# EEG_3.net
KiCad netlist of a schematic drawn in Altium Designer
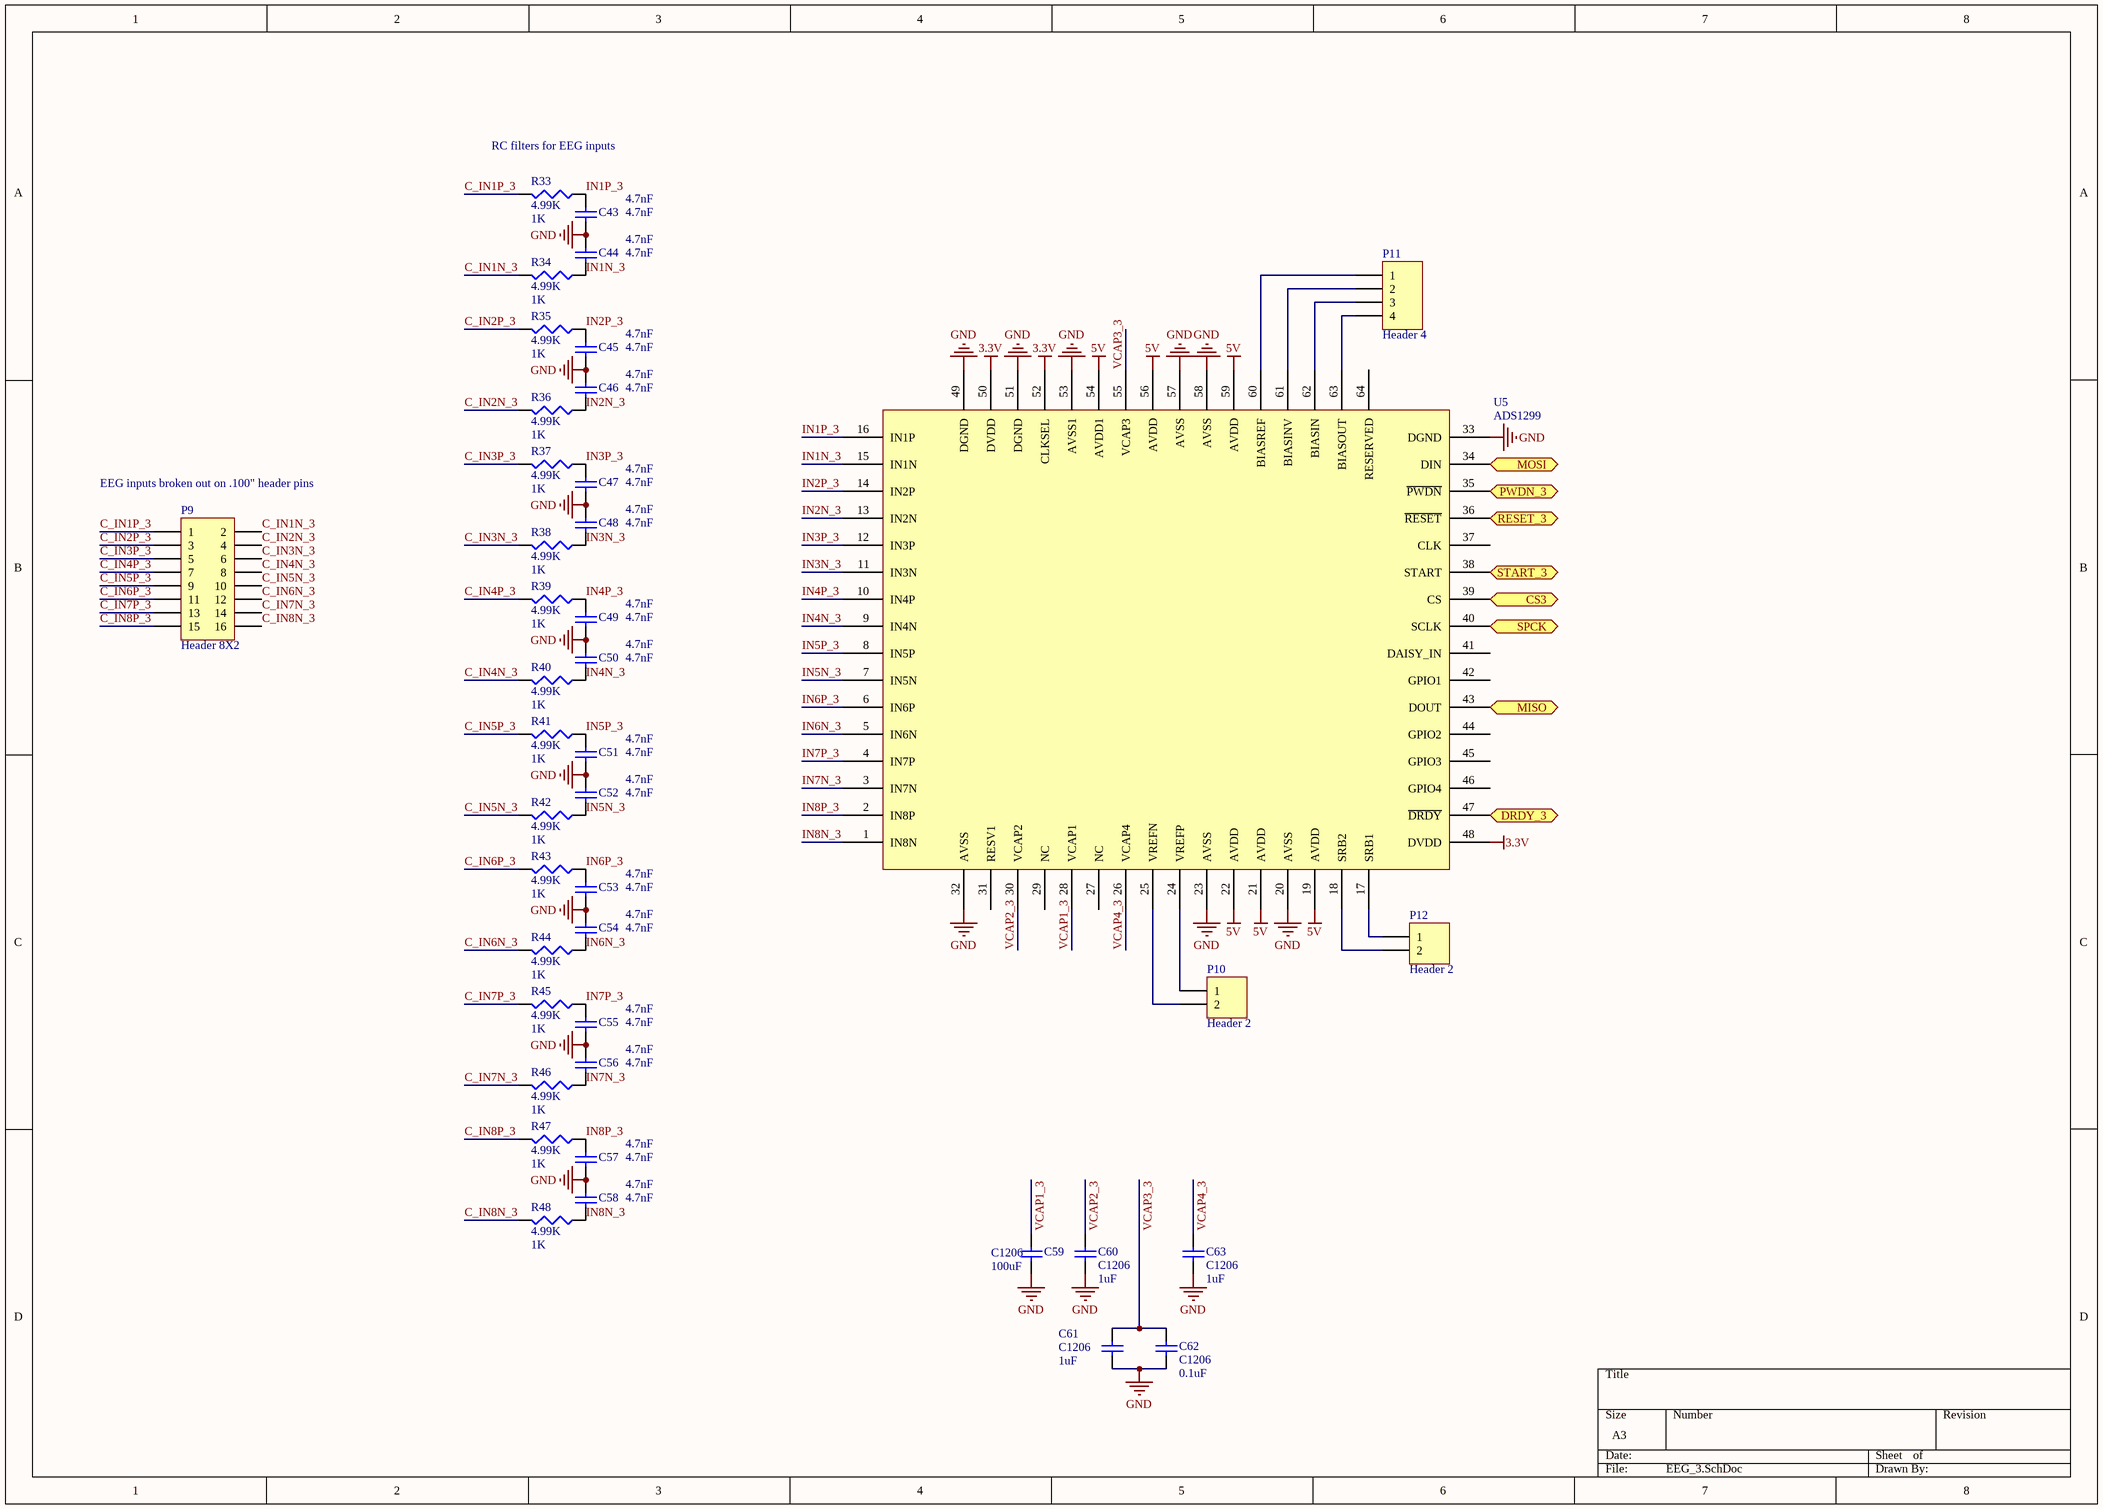
[diagram p0: EEG_3.SchDoc]

(export (version "E")
  (design (tool "Eeschema 10.0.6"))
  (components
    (comp (ref "C43")
      (value "4.7nF")
      (footprint "1608[0603]")
      (description "Capacitor (Semiconductor SIM Model)")
      (fields (field (name "ALTIUM_VALUE") "4.7nF") (field (name "PUBLISHER") "Altium Limited"))
      (libsource (lib "Miscellaneous Devices") (part "Cap Semi"))
    )
    (comp (ref "C44")
      (value "4.7nF")
      (footprint "1608[0603]")
      (description "Capacitor (Semiconductor SIM Model)")
      (fields (field (name "ALTIUM_VALUE") "4.7nF") (field (name "PUBLISHER") "Altium Limited"))
      (libsource (lib "Miscellaneous Devices") (part "Cap Semi"))
    )
    (comp (ref "C45")
      (value "4.7nF")
      (footprint "1608[0603]")
      (description "Capacitor (Semiconductor SIM Model)")
      (fields (field (name "ALTIUM_VALUE") "4.7nF") (field (name "PUBLISHER") "Altium Limited"))
      (libsource (lib "Miscellaneous Devices") (part "Cap Semi"))
    )
    (comp (ref "C46")
      (value "4.7nF")
      (footprint "1608[0603]")
      (description "Capacitor (Semiconductor SIM Model)")
      (fields (field (name "ALTIUM_VALUE") "4.7nF") (field (name "PUBLISHER") "Altium Limited"))
      (libsource (lib "Miscellaneous Devices") (part "Cap Semi"))
    )
    (comp (ref "C47")
      (value "4.7nF")
      (footprint "1608[0603]")
      (description "Capacitor (Semiconductor SIM Model)")
      (fields (field (name "ALTIUM_VALUE") "4.7nF") (field (name "PUBLISHER") "Altium Limited"))
      (libsource (lib "Miscellaneous Devices") (part "Cap Semi"))
    )
    (comp (ref "C48")
      (value "4.7nF")
      (footprint "1608[0603]")
      (description "Capacitor (Semiconductor SIM Model)")
      (fields (field (name "ALTIUM_VALUE") "4.7nF") (field (name "PUBLISHER") "Altium Limited"))
      (libsource (lib "Miscellaneous Devices") (part "Cap Semi"))
    )
    (comp (ref "C49")
      (value "4.7nF")
      (footprint "1608[0603]")
      (description "Capacitor (Semiconductor SIM Model)")
      (fields (field (name "ALTIUM_VALUE") "4.7nF") (field (name "PUBLISHER") "Altium Limited"))
      (libsource (lib "Miscellaneous Devices") (part "Cap Semi"))
    )
    (comp (ref "C50")
      (value "4.7nF")
      (footprint "1608[0603]")
      (description "Capacitor (Semiconductor SIM Model)")
      (fields (field (name "ALTIUM_VALUE") "4.7nF") (field (name "PUBLISHER") "Altium Limited"))
      (libsource (lib "Miscellaneous Devices") (part "Cap Semi"))
    )
    (comp (ref "C51")
      (value "4.7nF")
      (footprint "1608[0603]")
      (description "Capacitor (Semiconductor SIM Model)")
      (fields (field (name "ALTIUM_VALUE") "4.7nF") (field (name "PUBLISHER") "Altium Limited"))
      (libsource (lib "Miscellaneous Devices") (part "Cap Semi"))
    )
    (comp (ref "C52")
      (value "4.7nF")
      (footprint "1608[0603]")
      (description "Capacitor (Semiconductor SIM Model)")
      (fields (field (name "ALTIUM_VALUE") "4.7nF") (field (name "PUBLISHER") "Altium Limited"))
      (libsource (lib "Miscellaneous Devices") (part "Cap Semi"))
    )
    (comp (ref "C53")
      (value "4.7nF")
      (footprint "1608[0603]")
      (description "Capacitor (Semiconductor SIM Model)")
      (fields (field (name "ALTIUM_VALUE") "4.7nF") (field (name "PUBLISHER") "Altium Limited"))
      (libsource (lib "Miscellaneous Devices") (part "Cap Semi"))
    )
    (comp (ref "C54")
      (value "4.7nF")
      (footprint "1608[0603]")
      (description "Capacitor (Semiconductor SIM Model)")
      (fields (field (name "ALTIUM_VALUE") "4.7nF") (field (name "PUBLISHER") "Altium Limited"))
      (libsource (lib "Miscellaneous Devices") (part "Cap Semi"))
    )
    (comp (ref "C55")
      (value "4.7nF")
      (footprint "1608[0603]")
      (description "Capacitor (Semiconductor SIM Model)")
      (fields (field (name "ALTIUM_VALUE") "4.7nF") (field (name "PUBLISHER") "Altium Limited"))
      (libsource (lib "Miscellaneous Devices") (part "Cap Semi"))
    )
    (comp (ref "C56")
      (value "4.7nF")
      (footprint "1608[0603]")
      (description "Capacitor (Semiconductor SIM Model)")
      (fields (field (name "ALTIUM_VALUE") "4.7nF") (field (name "PUBLISHER") "Altium Limited"))
      (libsource (lib "Miscellaneous Devices") (part "Cap Semi"))
    )
    (comp (ref "C57")
      (value "4.7nF")
      (footprint "1608[0603]")
      (description "Capacitor (Semiconductor SIM Model)")
      (fields (field (name "ALTIUM_VALUE") "4.7nF") (field (name "PUBLISHER") "Altium Limited"))
      (libsource (lib "Miscellaneous Devices") (part "Cap Semi"))
    )
    (comp (ref "C58")
      (value "4.7nF")
      (footprint "1608[0603]")
      (description "Capacitor (Semiconductor SIM Model)")
      (fields (field (name "ALTIUM_VALUE") "4.7nF") (field (name "PUBLISHER") "Altium Limited"))
      (libsource (lib "Miscellaneous Devices") (part "Cap Semi"))
    )
    (comp (ref "C59")
      (value "C1206")
      (footprint "1608[0603]")
      (description "Capacitor (Semiconductor SIM Model)")
      (fields (field (name "ALTIUM_VALUE") "100uF") (field (name "PUBLISHER") "Altium Limited"))
      (libsource (lib "Miscellaneous Devices") (part "Cap Semi"))
    )
    (comp (ref "C60")
      (value "C1206")
      (footprint "1608[0603]")
      (description "Capacitor (Semiconductor SIM Model)")
      (fields (field (name "ALTIUM_VALUE") "1uF") (field (name "PUBLISHER") "Altium Limited"))
      (libsource (lib "Miscellaneous Devices") (part "Cap Semi"))
    )
    (comp (ref "C61")
      (value "C1206")
      (footprint "1608[0603]")
      (description "Capacitor (Semiconductor SIM Model)")
      (fields (field (name "ALTIUM_VALUE") "1uF") (field (name "PUBLISHER") "Altium Limited"))
      (libsource (lib "Miscellaneous Devices") (part "Cap Semi"))
    )
    (comp (ref "C62")
      (value "C1206")
      (footprint "1608[0603]")
      (description "Capacitor (Semiconductor SIM Model)")
      (fields (field (name "ALTIUM_VALUE") "0.1uF") (field (name "PUBLISHER") "Altium Limited"))
      (libsource (lib "Miscellaneous Devices") (part "Cap Semi"))
    )
    (comp (ref "C63")
      (value "C1206")
      (footprint "1608[0603]")
      (description "Capacitor (Semiconductor SIM Model)")
      (fields (field (name "ALTIUM_VALUE") "1uF") (field (name "PUBLISHER") "Altium Limited"))
      (libsource (lib "Miscellaneous Devices") (part "Cap Semi"))
    )
    (comp (ref "P9")
      (value "Header 8X2")
      (footprint "HDR2X8")
      (description "Header, 8-Pin, Dual row")
      (fields (field (name "PUBLISHER") "Altium Limited"))
      (libsource (lib "Miscellaneous Connectors") (part "Header 8X2"))
    )
    (comp (ref "P10")
      (value "Header 2")
      (footprint "HDR1X2")
      (description "Header, 2-Pin")
      (fields (field (name "PUBLISHER") "Altium Limited"))
      (libsource (lib "Miscellaneous Connectors") (part "Header 2"))
    )
    (comp (ref "P11")
      (value "Header 4")
      (footprint "HDR1X4")
      (description "Header, 4-Pin")
      (fields (field (name "PUBLISHER") "Altium Limited"))
      (libsource (lib "Miscellaneous Connectors") (part "Header 4"))
    )
    (comp (ref "P12")
      (value "Header 2")
      (footprint "HDR1X2")
      (description "Header, 2-Pin")
      (fields (field (name "PUBLISHER") "Altium Limited"))
      (libsource (lib "Miscellaneous Connectors") (part "Header 2"))
    )
    (comp (ref "R33")
      (value "4.99K")
      (footprint "1608[0603]")
      (description "Resistor")
      (fields (field (name "ALTIUM_VALUE") "1K") (field (name "PUBLISHER") "Altium Limited"))
      (libsource (lib "Miscellaneous Devices") (part "Res3"))
    )
    (comp (ref "R34")
      (value "4.99K")
      (footprint "1608[0603]")
      (description "Resistor")
      (fields (field (name "ALTIUM_VALUE") "1K") (field (name "PUBLISHER") "Altium Limited"))
      (libsource (lib "Miscellaneous Devices") (part "Res3"))
    )
    (comp (ref "R35")
      (value "4.99K")
      (footprint "1608[0603]")
      (description "Resistor")
      (fields (field (name "ALTIUM_VALUE") "1K") (field (name "PUBLISHER") "Altium Limited"))
      (libsource (lib "Miscellaneous Devices") (part "Res3"))
    )
    (comp (ref "R36")
      (value "4.99K")
      (footprint "1608[0603]")
      (description "Resistor")
      (fields (field (name "ALTIUM_VALUE") "1K") (field (name "PUBLISHER") "Altium Limited"))
      (libsource (lib "Miscellaneous Devices") (part "Res3"))
    )
    (comp (ref "R37")
      (value "4.99K")
      (footprint "1608[0603]")
      (description "Resistor")
      (fields (field (name "ALTIUM_VALUE") "1K") (field (name "PUBLISHER") "Altium Limited"))
      (libsource (lib "Miscellaneous Devices") (part "Res3"))
    )
    (comp (ref "R38")
      (value "4.99K")
      (footprint "1608[0603]")
      (description "Resistor")
      (fields (field (name "ALTIUM_VALUE") "1K") (field (name "PUBLISHER") "Altium Limited"))
      (libsource (lib "Miscellaneous Devices") (part "Res3"))
    )
    (comp (ref "R39")
      (value "4.99K")
      (footprint "1608[0603]")
      (description "Resistor")
      (fields (field (name "ALTIUM_VALUE") "1K") (field (name "PUBLISHER") "Altium Limited"))
      (libsource (lib "Miscellaneous Devices") (part "Res3"))
    )
    (comp (ref "R40")
      (value "4.99K")
      (footprint "1608[0603]")
      (description "Resistor")
      (fields (field (name "ALTIUM_VALUE") "1K") (field (name "PUBLISHER") "Altium Limited"))
      (libsource (lib "Miscellaneous Devices") (part "Res3"))
    )
    (comp (ref "R41")
      (value "4.99K")
      (footprint "1608[0603]")
      (description "Resistor")
      (fields (field (name "ALTIUM_VALUE") "1K") (field (name "PUBLISHER") "Altium Limited"))
      (libsource (lib "Miscellaneous Devices") (part "Res3"))
    )
    (comp (ref "R42")
      (value "4.99K")
      (footprint "1608[0603]")
      (description "Resistor")
      (fields (field (name "ALTIUM_VALUE") "1K") (field (name "PUBLISHER") "Altium Limited"))
      (libsource (lib "Miscellaneous Devices") (part "Res3"))
    )
    (comp (ref "R43")
      (value "4.99K")
      (footprint "1608[0603]")
      (description "Resistor")
      (fields (field (name "ALTIUM_VALUE") "1K") (field (name "PUBLISHER") "Altium Limited"))
      (libsource (lib "Miscellaneous Devices") (part "Res3"))
    )
    (comp (ref "R44")
      (value "4.99K")
      (footprint "1608[0603]")
      (description "Resistor")
      (fields (field (name "ALTIUM_VALUE") "1K") (field (name "PUBLISHER") "Altium Limited"))
      (libsource (lib "Miscellaneous Devices") (part "Res3"))
    )
    (comp (ref "R45")
      (value "4.99K")
      (footprint "1608[0603]")
      (description "Resistor")
      (fields (field (name "ALTIUM_VALUE") "1K") (field (name "PUBLISHER") "Altium Limited"))
      (libsource (lib "Miscellaneous Devices") (part "Res3"))
    )
    (comp (ref "R46")
      (value "4.99K")
      (footprint "1608[0603]")
      (description "Resistor")
      (fields (field (name "ALTIUM_VALUE") "1K") (field (name "PUBLISHER") "Altium Limited"))
      (libsource (lib "Miscellaneous Devices") (part "Res3"))
    )
    (comp (ref "R47")
      (value "4.99K")
      (footprint "1608[0603]")
      (description "Resistor")
      (fields (field (name "ALTIUM_VALUE") "1K") (field (name "PUBLISHER") "Altium Limited"))
      (libsource (lib "Miscellaneous Devices") (part "Res3"))
    )
    (comp (ref "R48")
      (value "4.99K")
      (footprint "1608[0603]")
      (description "Resistor")
      (fields (field (name "ALTIUM_VALUE") "1K") (field (name "PUBLISHER") "Altium Limited"))
      (libsource (lib "Miscellaneous Devices") (part "Res3"))
    )
    (comp (ref "U5")
      (value "ADS1299")
      (footprint "ADS1299 Plastic QFP")
      (libsource (lib "ADS1299") (part "ADS1299"))
    )
  )
  (nets
    (net (code "1") (name "/CS3") (class "Default")
      (node (ref "U5") (pin "39") (pinfunction "CS_39") (pintype "passive"))
    )
    (net (code "2") (name "/C_IN1N_3") (class "Default")
      (node (ref "P9") (pin "2") (pinfunction "2_2") (pintype "passive"))
      (node (ref "R34") (pin "2") (pinfunction "2_2") (pintype "passive"))
    )
    (net (code "3") (name "/C_IN1P_3") (class "Default")
      (node (ref "P9") (pin "1") (pinfunction "1_1") (pintype "passive"))
      (node (ref "R33") (pin "2") (pinfunction "2_2") (pintype "passive"))
    )
    (net (code "4") (name "/C_IN2N_3") (class "Default")
      (node (ref "P9") (pin "4") (pinfunction "4_4") (pintype "passive"))
      (node (ref "R36") (pin "2") (pinfunction "2_2") (pintype "passive"))
    )
    (net (code "5") (name "/C_IN2P_3") (class "Default")
      (node (ref "P9") (pin "3") (pinfunction "3_3") (pintype "passive"))
      (node (ref "R35") (pin "2") (pinfunction "2_2") (pintype "passive"))
    )
    (net (code "6") (name "/C_IN3N_3") (class "Default")
      (node (ref "P9") (pin "6") (pinfunction "6_6") (pintype "passive"))
      (node (ref "R38") (pin "2") (pinfunction "2_2") (pintype "passive"))
    )
    (net (code "7") (name "/C_IN3P_3") (class "Default")
      (node (ref "P9") (pin "5") (pinfunction "5_5") (pintype "passive"))
      (node (ref "R37") (pin "2") (pinfunction "2_2") (pintype "passive"))
    )
    (net (code "8") (name "/C_IN4N_3") (class "Default")
      (node (ref "P9") (pin "8") (pinfunction "8_8") (pintype "passive"))
      (node (ref "R40") (pin "2") (pinfunction "2_2") (pintype "passive"))
    )
    (net (code "9") (name "/C_IN4P_3") (class "Default")
      (node (ref "P9") (pin "7") (pinfunction "7_7") (pintype "passive"))
      (node (ref "R39") (pin "2") (pinfunction "2_2") (pintype "passive"))
    )
    (net (code "10") (name "/C_IN5N_3") (class "Default")
      (node (ref "P9") (pin "10") (pinfunction "10_10") (pintype "passive"))
      (node (ref "R42") (pin "2") (pinfunction "2_2") (pintype "passive"))
    )
    (net (code "11") (name "/C_IN5P_3") (class "Default")
      (node (ref "P9") (pin "9") (pinfunction "9_9") (pintype "passive"))
      (node (ref "R41") (pin "2") (pinfunction "2_2") (pintype "passive"))
    )
    (net (code "12") (name "/C_IN6N_3") (class "Default")
      (node (ref "P9") (pin "12") (pinfunction "12_12") (pintype "passive"))
      (node (ref "R44") (pin "2") (pinfunction "2_2") (pintype "passive"))
    )
    (net (code "13") (name "/C_IN6P_3") (class "Default")
      (node (ref "P9") (pin "11") (pinfunction "11_11") (pintype "passive"))
      (node (ref "R43") (pin "2") (pinfunction "2_2") (pintype "passive"))
    )
    (net (code "14") (name "/C_IN7N_3") (class "Default")
      (node (ref "P9") (pin "14") (pinfunction "14_14") (pintype "passive"))
      (node (ref "R46") (pin "2") (pinfunction "2_2") (pintype "passive"))
    )
    (net (code "15") (name "/C_IN7P_3") (class "Default")
      (node (ref "P9") (pin "13") (pinfunction "13_13") (pintype "passive"))
      (node (ref "R45") (pin "2") (pinfunction "2_2") (pintype "passive"))
    )
    (net (code "16") (name "/C_IN8N_3") (class "Default")
      (node (ref "P9") (pin "16") (pinfunction "16_16") (pintype "passive"))
      (node (ref "R48") (pin "2") (pinfunction "2_2") (pintype "passive"))
    )
    (net (code "17") (name "/C_IN8P_3") (class "Default")
      (node (ref "P9") (pin "15") (pinfunction "15_15") (pintype "passive"))
      (node (ref "R47") (pin "2") (pinfunction "2_2") (pintype "passive"))
    )
    (net (code "18") (name "/DRDY_3") (class "Default")
      (node (ref "U5") (pin "47") (pinfunction "~{DRDY}_47") (pintype "passive"))
    )
    (net (code "19") (name "/IN1N_3") (class "Default")
      (node (ref "C44") (pin "1") (pinfunction "1_1") (pintype "passive"))
      (node (ref "R34") (pin "1") (pinfunction "1_1") (pintype "passive"))
      (node (ref "U5") (pin "15") (pinfunction "IN1N_15") (pintype "passive"))
    )
    (net (code "20") (name "/IN1P_3") (class "Default")
      (node (ref "C43") (pin "2") (pinfunction "2_2") (pintype "passive"))
      (node (ref "R33") (pin "1") (pinfunction "1_1") (pintype "passive"))
      (node (ref "U5") (pin "16") (pinfunction "IN1P_16") (pintype "passive"))
    )
    (net (code "21") (name "/IN2N_3") (class "Default")
      (node (ref "C46") (pin "1") (pinfunction "1_1") (pintype "passive"))
      (node (ref "R36") (pin "1") (pinfunction "1_1") (pintype "passive"))
      (node (ref "U5") (pin "13") (pinfunction "IN2N_13") (pintype "passive"))
    )
    (net (code "22") (name "/IN2P_3") (class "Default")
      (node (ref "C45") (pin "2") (pinfunction "2_2") (pintype "passive"))
      (node (ref "R35") (pin "1") (pinfunction "1_1") (pintype "passive"))
      (node (ref "U5") (pin "14") (pinfunction "IN2P_14") (pintype "passive"))
    )
    (net (code "23") (name "/IN3N_3") (class "Default")
      (node (ref "C48") (pin "1") (pinfunction "1_1") (pintype "passive"))
      (node (ref "R38") (pin "1") (pinfunction "1_1") (pintype "passive"))
      (node (ref "U5") (pin "11") (pinfunction "IN3N_11") (pintype "passive"))
    )
    (net (code "24") (name "/IN3P_3") (class "Default")
      (node (ref "C47") (pin "2") (pinfunction "2_2") (pintype "passive"))
      (node (ref "R37") (pin "1") (pinfunction "1_1") (pintype "passive"))
      (node (ref "U5") (pin "12") (pinfunction "IN3P_12") (pintype "passive"))
    )
    (net (code "25") (name "/IN4N_3") (class "Default")
      (node (ref "C50") (pin "1") (pinfunction "1_1") (pintype "passive"))
      (node (ref "R40") (pin "1") (pinfunction "1_1") (pintype "passive"))
      (node (ref "U5") (pin "9") (pinfunction "IN4N_9") (pintype "passive"))
    )
    (net (code "26") (name "/IN4P_3") (class "Default")
      (node (ref "C49") (pin "2") (pinfunction "2_2") (pintype "passive"))
      (node (ref "R39") (pin "1") (pinfunction "1_1") (pintype "passive"))
      (node (ref "U5") (pin "10") (pinfunction "IN4P_10") (pintype "passive"))
    )
    (net (code "27") (name "/IN5N_3") (class "Default")
      (node (ref "C52") (pin "1") (pinfunction "1_1") (pintype "passive"))
      (node (ref "R42") (pin "1") (pinfunction "1_1") (pintype "passive"))
      (node (ref "U5") (pin "7") (pinfunction "IN5N_7") (pintype "passive"))
    )
    (net (code "28") (name "/IN5P_3") (class "Default")
      (node (ref "C51") (pin "2") (pinfunction "2_2") (pintype "passive"))
      (node (ref "R41") (pin "1") (pinfunction "1_1") (pintype "passive"))
      (node (ref "U5") (pin "8") (pinfunction "IN5P_8") (pintype "passive"))
    )
    (net (code "29") (name "/IN6N_3") (class "Default")
      (node (ref "C54") (pin "1") (pinfunction "1_1") (pintype "passive"))
      (node (ref "R44") (pin "1") (pinfunction "1_1") (pintype "passive"))
      (node (ref "U5") (pin "5") (pinfunction "IN6N_5") (pintype "passive"))
    )
    (net (code "30") (name "/IN6P_3") (class "Default")
      (node (ref "C53") (pin "2") (pinfunction "2_2") (pintype "passive"))
      (node (ref "R43") (pin "1") (pinfunction "1_1") (pintype "passive"))
      (node (ref "U5") (pin "6") (pinfunction "IN6P_6") (pintype "passive"))
    )
    (net (code "31") (name "/IN7N_3") (class "Default")
      (node (ref "C56") (pin "1") (pinfunction "1_1") (pintype "passive"))
      (node (ref "R46") (pin "1") (pinfunction "1_1") (pintype "passive"))
      (node (ref "U5") (pin "3") (pinfunction "IN7N_3") (pintype "passive"))
    )
    (net (code "32") (name "/IN7P_3") (class "Default")
      (node (ref "C55") (pin "2") (pinfunction "2_2") (pintype "passive"))
      (node (ref "R45") (pin "1") (pinfunction "1_1") (pintype "passive"))
      (node (ref "U5") (pin "4") (pinfunction "IN7P_4") (pintype "passive"))
    )
    (net (code "33") (name "/IN8N_3") (class "Default")
      (node (ref "C58") (pin "1") (pinfunction "1_1") (pintype "passive"))
      (node (ref "R48") (pin "1") (pinfunction "1_1") (pintype "passive"))
      (node (ref "U5") (pin "1") (pinfunction "IN8N_1") (pintype "passive"))
    )
    (net (code "34") (name "/IN8P_3") (class "Default")
      (node (ref "C57") (pin "2") (pinfunction "2_2") (pintype "passive"))
      (node (ref "R47") (pin "1") (pinfunction "1_1") (pintype "passive"))
      (node (ref "U5") (pin "2") (pinfunction "IN8P_2") (pintype "passive"))
    )
    (net (code "35") (name "/MISO") (class "Default")
      (node (ref "U5") (pin "43") (pinfunction "DOUT_43") (pintype "passive"))
    )
    (net (code "36") (name "/MOSI") (class "Default")
      (node (ref "U5") (pin "34") (pinfunction "DIN_34") (pintype "passive"))
    )
    (net (code "37") (name "/PWDN_3") (class "Default")
      (node (ref "U5") (pin "35") (pinfunction "~{PWDN}_35") (pintype "passive"))
    )
    (net (code "38") (name "/RESET_3") (class "Default")
      (node (ref "U5") (pin "36") (pinfunction "~{RESET}_36") (pintype "passive"))
    )
    (net (code "39") (name "/SPCK") (class "Default")
      (node (ref "U5") (pin "40") (pinfunction "SCLK_40") (pintype "passive"))
    )
    (net (code "40") (name "/START_3") (class "Default")
      (node (ref "U5") (pin "38") (pinfunction "START_38") (pintype "passive"))
    )
    (net (code "41") (name "/VCAP1_3") (class "Default")
      (node (ref "C59") (pin "1") (pinfunction "1_1") (pintype "passive"))
      (node (ref "U5") (pin "28") (pinfunction "VCAP1_28") (pintype "passive"))
    )
    (net (code "42") (name "/VCAP2_3") (class "Default")
      (node (ref "C60") (pin "2") (pinfunction "2_2") (pintype "passive"))
      (node (ref "U5") (pin "30") (pinfunction "VCAP2_30") (pintype "passive"))
    )
    (net (code "43") (name "/VCAP3_3") (class "Default")
      (node (ref "C61") (pin "1") (pinfunction "1_1") (pintype "passive"))
      (node (ref "C62") (pin "2") (pinfunction "2_2") (pintype "passive"))
      (node (ref "U5") (pin "55") (pinfunction "VCAP3_55") (pintype "passive"))
    )
    (net (code "44") (name "/VCAP4_3") (class "Default")
      (node (ref "C63") (pin "2") (pinfunction "2_2") (pintype "passive"))
      (node (ref "U5") (pin "26") (pinfunction "VCAP4_26") (pintype "passive"))
    )
    (net (code "45") (name "3.3V") (class "Default")
      (node (ref "U5") (pin "48") (pinfunction "DVDD_48") (pintype "passive"))
      (node (ref "U5") (pin "50") (pinfunction "DVDD_50") (pintype "passive"))
      (node (ref "U5") (pin "52") (pinfunction "CLKSEL_52") (pintype "passive"))
    )
    (net (code "46") (name "5V") (class "Default")
      (node (ref "U5") (pin "19") (pinfunction "AVDD_19") (pintype "passive"))
      (node (ref "U5") (pin "21") (pinfunction "AVDD_21") (pintype "passive"))
      (node (ref "U5") (pin "22") (pinfunction "AVDD_22") (pintype "passive"))
      (node (ref "U5") (pin "54") (pinfunction "AVDD1_54") (pintype "passive"))
      (node (ref "U5") (pin "56") (pinfunction "AVDD_56") (pintype "passive"))
      (node (ref "U5") (pin "59") (pinfunction "AVDD_59") (pintype "passive"))
    )
    (net (code "47") (name "GND") (class "Default")
      (node (ref "C43") (pin "1") (pinfunction "1_1") (pintype "passive"))
      (node (ref "C44") (pin "2") (pinfunction "2_2") (pintype "passive"))
      (node (ref "C45") (pin "1") (pinfunction "1_1") (pintype "passive"))
      (node (ref "C46") (pin "2") (pinfunction "2_2") (pintype "passive"))
      (node (ref "C47") (pin "1") (pinfunction "1_1") (pintype "passive"))
      (node (ref "C48") (pin "2") (pinfunction "2_2") (pintype "passive"))
      (node (ref "C49") (pin "1") (pinfunction "1_1") (pintype "passive"))
      (node (ref "C50") (pin "2") (pinfunction "2_2") (pintype "passive"))
      (node (ref "C51") (pin "1") (pinfunction "1_1") (pintype "passive"))
      (node (ref "C52") (pin "2") (pinfunction "2_2") (pintype "passive"))
      (node (ref "C53") (pin "1") (pinfunction "1_1") (pintype "passive"))
      (node (ref "C54") (pin "2") (pinfunction "2_2") (pintype "passive"))
      (node (ref "C55") (pin "1") (pinfunction "1_1") (pintype "passive"))
      (node (ref "C56") (pin "2") (pinfunction "2_2") (pintype "passive"))
      (node (ref "C57") (pin "1") (pinfunction "1_1") (pintype "passive"))
      (node (ref "C58") (pin "2") (pinfunction "2_2") (pintype "passive"))
      (node (ref "C59") (pin "2") (pinfunction "2_2") (pintype "passive"))
      (node (ref "C60") (pin "1") (pinfunction "1_1") (pintype "passive"))
      (node (ref "C61") (pin "2") (pinfunction "2_2") (pintype "passive"))
      (node (ref "C62") (pin "1") (pinfunction "1_1") (pintype "passive"))
      (node (ref "C63") (pin "1") (pinfunction "1_1") (pintype "passive"))
      (node (ref "U5") (pin "20") (pinfunction "AVSS_20") (pintype "passive"))
      (node (ref "U5") (pin "23") (pinfunction "AVSS_23") (pintype "passive"))
      (node (ref "U5") (pin "32") (pinfunction "AVSS_32") (pintype "passive"))
      (node (ref "U5") (pin "33") (pinfunction "DGND_33") (pintype "passive"))
      (node (ref "U5") (pin "49") (pinfunction "DGND_49") (pintype "passive"))
      (node (ref "U5") (pin "51") (pinfunction "DGND_51") (pintype "passive"))
      (node (ref "U5") (pin "53") (pinfunction "AVSS1_53") (pintype "passive"))
      (node (ref "U5") (pin "57") (pinfunction "AVSS_57") (pintype "passive"))
      (node (ref "U5") (pin "58") (pinfunction "AVSS_58") (pintype "passive"))
    )
    (net (code "48") (name "Net-(U5-BIASIN)") (class "Default")
      (node (ref "P11") (pin "3") (pinfunction "3_3") (pintype "passive"))
      (node (ref "U5") (pin "62") (pinfunction "BIASIN_62") (pintype "passive"))
    )
    (net (code "49") (name "Net-(U5-BIASINV)") (class "Default")
      (node (ref "P11") (pin "2") (pinfunction "2_2") (pintype "passive"))
      (node (ref "U5") (pin "61") (pinfunction "BIASINV_61") (pintype "passive"))
    )
    (net (code "50") (name "Net-(U5-BIASOUT)") (class "Default")
      (node (ref "P11") (pin "4") (pinfunction "4_4") (pintype "passive"))
      (node (ref "U5") (pin "63") (pinfunction "BIASOUT_63") (pintype "passive"))
    )
    (net (code "51") (name "Net-(U5-BIASREF)") (class "Default")
      (node (ref "P11") (pin "1") (pinfunction "1_1") (pintype "passive"))
      (node (ref "U5") (pin "60") (pinfunction "BIASREF_60") (pintype "passive"))
    )
    (net (code "52") (name "Net-(U5-SRB1)") (class "Default")
      (node (ref "P12") (pin "1") (pinfunction "1_1") (pintype "passive"))
      (node (ref "U5") (pin "17") (pinfunction "SRB1_17") (pintype "passive"))
    )
    (net (code "53") (name "Net-(U5-SRB2)") (class "Default")
      (node (ref "P12") (pin "2") (pinfunction "2_2") (pintype "passive"))
      (node (ref "U5") (pin "18") (pinfunction "SRB2_18") (pintype "passive"))
    )
    (net (code "54") (name "Net-(U5-VREFN)") (class "Default")
      (node (ref "P10") (pin "2") (pinfunction "2_2") (pintype "passive"))
      (node (ref "U5") (pin "25") (pinfunction "VREFN_25") (pintype "passive"))
    )
    (net (code "55") (name "Net-(U5-VREFP)") (class "Default")
      (node (ref "P10") (pin "1") (pinfunction "1_1") (pintype "passive"))
      (node (ref "U5") (pin "24") (pinfunction "VREFP_24") (pintype "passive"))
    )
    (net (code "56") (name "unconnected-(U5-CLK-Pad37)") (class "Default")
      (node (ref "U5") (pin "37") (pinfunction "CLK_37") (pintype "passive"))
    )
    (net (code "57") (name "unconnected-(U5-DAISY_IN-Pad41)") (class "Default")
      (node (ref "U5") (pin "41") (pinfunction "DAISY_IN_41") (pintype "passive"))
    )
    (net (code "58") (name "unconnected-(U5-GPIO1-Pad42)") (class "Default")
      (node (ref "U5") (pin "42") (pinfunction "GPIO1_42") (pintype "passive"))
    )
    (net (code "59") (name "unconnected-(U5-GPIO2-Pad44)") (class "Default")
      (node (ref "U5") (pin "44") (pinfunction "GPIO2_44") (pintype "passive"))
    )
    (net (code "60") (name "unconnected-(U5-GPIO3-Pad45)") (class "Default")
      (node (ref "U5") (pin "45") (pinfunction "GPIO3_45") (pintype "passive"))
    )
    (net (code "61") (name "unconnected-(U5-GPIO4-Pad46)") (class "Default")
      (node (ref "U5") (pin "46") (pinfunction "GPIO4_46") (pintype "passive"))
    )
    (net (code "62") (name "unconnected-(U5-NC-Pad27)") (class "Default")
      (node (ref "U5") (pin "27") (pinfunction "NC_27") (pintype "passive"))
    )
    (net (code "63") (name "unconnected-(U5-NC-Pad29)") (class "Default")
      (node (ref "U5") (pin "29") (pinfunction "NC_29") (pintype "passive"))
    )
    (net (code "64") (name "unconnected-(U5-RESERVED-Pad64)") (class "Default")
      (node (ref "U5") (pin "64") (pinfunction "RESERVED_64") (pintype "passive"))
    )
    (net (code "65") (name "unconnected-(U5-RESV1-Pad31)") (class "Default")
      (node (ref "U5") (pin "31") (pinfunction "RESV1_31") (pintype "passive"))
    )
  )
)
